# top.net
KiCad netlist of a schematic drawn in Altium Designer
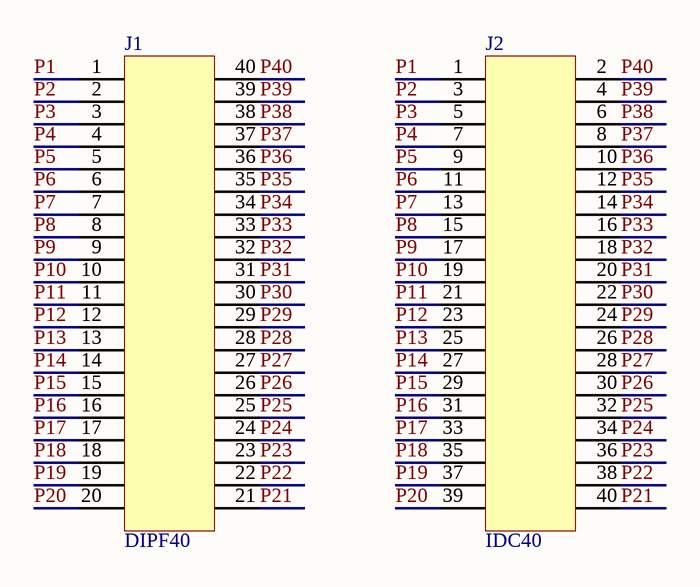
[diagram p0: top.SchDoc]

(export (version "E")
  (design (tool "Eeschema 10.0.6"))
  (components
    (comp (ref "J1")
      (value "DIPF40")
      (footprint "DIPF40")
      (description "DIP40 ZIF")
      (libsource (lib "schmlib") (part "DIPF40"))
    )
    (comp (ref "J2") (value "IDC40") (footprint "IDC40") (libsource (lib "schmlib") (part "IDC40")))
  )
  (nets
    (net (code "1") (name "/P1") (class "Default")
      (node (ref "J1") (pin "1") (pinfunction "1_1") (pintype "passive"))
      (node (ref "J2") (pin "1") (pinfunction "1_1") (pintype "passive"))
    )
    (net (code "2") (name "/P2") (class "Default")
      (node (ref "J1") (pin "2") (pinfunction "2_2") (pintype "passive"))
      (node (ref "J2") (pin "3") (pinfunction "3_3") (pintype "passive"))
    )
    (net (code "3") (name "/P3") (class "Default")
      (node (ref "J1") (pin "3") (pinfunction "3_3") (pintype "passive"))
      (node (ref "J2") (pin "5") (pinfunction "5_5") (pintype "passive"))
    )
    (net (code "4") (name "/P4") (class "Default")
      (node (ref "J1") (pin "4") (pinfunction "4_4") (pintype "passive"))
      (node (ref "J2") (pin "7") (pinfunction "7_7") (pintype "passive"))
    )
    (net (code "5") (name "/P5") (class "Default")
      (node (ref "J1") (pin "5") (pinfunction "5_5") (pintype "passive"))
      (node (ref "J2") (pin "9") (pinfunction "9_9") (pintype "passive"))
    )
    (net (code "6") (name "/P6") (class "Default")
      (node (ref "J1") (pin "6") (pinfunction "6_6") (pintype "passive"))
      (node (ref "J2") (pin "11") (pinfunction "11_11") (pintype "passive"))
    )
    (net (code "7") (name "/P7") (class "Default")
      (node (ref "J1") (pin "7") (pinfunction "7_7") (pintype "passive"))
      (node (ref "J2") (pin "13") (pinfunction "13_13") (pintype "passive"))
    )
    (net (code "8") (name "/P8") (class "Default")
      (node (ref "J1") (pin "8") (pinfunction "8_8") (pintype "passive"))
      (node (ref "J2") (pin "15") (pinfunction "15_15") (pintype "passive"))
    )
    (net (code "9") (name "/P9") (class "Default")
      (node (ref "J1") (pin "9") (pinfunction "9_9") (pintype "passive"))
      (node (ref "J2") (pin "17") (pinfunction "17_17") (pintype "passive"))
    )
    (net (code "10") (name "/P10") (class "Default")
      (node (ref "J1") (pin "10") (pinfunction "10_10") (pintype "passive"))
      (node (ref "J2") (pin "19") (pinfunction "19_19") (pintype "passive"))
    )
    (net (code "11") (name "/P11") (class "Default")
      (node (ref "J1") (pin "11") (pinfunction "11_11") (pintype "passive"))
      (node (ref "J2") (pin "21") (pinfunction "21_21") (pintype "passive"))
    )
    (net (code "12") (name "/P12") (class "Default")
      (node (ref "J1") (pin "12") (pinfunction "12_12") (pintype "passive"))
      (node (ref "J2") (pin "23") (pinfunction "23_23") (pintype "passive"))
    )
    (net (code "13") (name "/P13") (class "Default")
      (node (ref "J1") (pin "13") (pinfunction "13_13") (pintype "passive"))
      (node (ref "J2") (pin "25") (pinfunction "25_25") (pintype "passive"))
    )
    (net (code "14") (name "/P14") (class "Default")
      (node (ref "J1") (pin "14") (pinfunction "14_14") (pintype "passive"))
      (node (ref "J2") (pin "27") (pinfunction "27_27") (pintype "passive"))
    )
    (net (code "15") (name "/P15") (class "Default")
      (node (ref "J1") (pin "15") (pinfunction "15_15") (pintype "passive"))
      (node (ref "J2") (pin "29") (pinfunction "29_29") (pintype "passive"))
    )
    (net (code "16") (name "/P16") (class "Default")
      (node (ref "J1") (pin "16") (pinfunction "16_16") (pintype "passive"))
      (node (ref "J2") (pin "31") (pinfunction "31_31") (pintype "passive"))
    )
    (net (code "17") (name "/P17") (class "Default")
      (node (ref "J1") (pin "17") (pinfunction "17_17") (pintype "passive"))
      (node (ref "J2") (pin "33") (pinfunction "33_33") (pintype "passive"))
    )
    (net (code "18") (name "/P18") (class "Default")
      (node (ref "J1") (pin "18") (pinfunction "18_18") (pintype "passive"))
      (node (ref "J2") (pin "35") (pinfunction "35_35") (pintype "passive"))
    )
    (net (code "19") (name "/P19") (class "Default")
      (node (ref "J1") (pin "19") (pinfunction "19_19") (pintype "passive"))
      (node (ref "J2") (pin "37") (pinfunction "37_37") (pintype "passive"))
    )
    (net (code "20") (name "/P20") (class "Default")
      (node (ref "J1") (pin "20") (pinfunction "20_20") (pintype "passive"))
      (node (ref "J2") (pin "39") (pinfunction "39_39") (pintype "passive"))
    )
    (net (code "21") (name "/P21") (class "Default")
      (node (ref "J1") (pin "21") (pinfunction "21_21") (pintype "passive"))
      (node (ref "J2") (pin "40") (pinfunction "40_40") (pintype "passive"))
    )
    (net (code "22") (name "/P22") (class "Default")
      (node (ref "J1") (pin "22") (pinfunction "22_22") (pintype "passive"))
      (node (ref "J2") (pin "38") (pinfunction "38_38") (pintype "passive"))
    )
    (net (code "23") (name "/P23") (class "Default")
      (node (ref "J1") (pin "23") (pinfunction "23_23") (pintype "passive"))
      (node (ref "J2") (pin "36") (pinfunction "36_36") (pintype "passive"))
    )
    (net (code "24") (name "/P24") (class "Default")
      (node (ref "J1") (pin "24") (pinfunction "24_24") (pintype "passive"))
      (node (ref "J2") (pin "34") (pinfunction "34_34") (pintype "passive"))
    )
    (net (code "25") (name "/P25") (class "Default")
      (node (ref "J1") (pin "25") (pinfunction "25_25") (pintype "passive"))
      (node (ref "J2") (pin "32") (pinfunction "32_32") (pintype "passive"))
    )
    (net (code "26") (name "/P26") (class "Default")
      (node (ref "J1") (pin "26") (pinfunction "26_26") (pintype "passive"))
      (node (ref "J2") (pin "30") (pinfunction "30_30") (pintype "passive"))
    )
    (net (code "27") (name "/P27") (class "Default")
      (node (ref "J1") (pin "27") (pinfunction "27_27") (pintype "passive"))
      (node (ref "J2") (pin "28") (pinfunction "28_28") (pintype "passive"))
    )
    (net (code "28") (name "/P28") (class "Default")
      (node (ref "J1") (pin "28") (pinfunction "28_28") (pintype "passive"))
      (node (ref "J2") (pin "26") (pinfunction "26_26") (pintype "passive"))
    )
    (net (code "29") (name "/P29") (class "Default")
      (node (ref "J1") (pin "29") (pinfunction "29_29") (pintype "passive"))
      (node (ref "J2") (pin "24") (pinfunction "24_24") (pintype "passive"))
    )
    (net (code "30") (name "/P30") (class "Default")
      (node (ref "J1") (pin "30") (pinfunction "30_30") (pintype "passive"))
      (node (ref "J2") (pin "22") (pinfunction "22_22") (pintype "passive"))
    )
    (net (code "31") (name "/P31") (class "Default")
      (node (ref "J1") (pin "31") (pinfunction "31_31") (pintype "passive"))
      (node (ref "J2") (pin "20") (pinfunction "20_20") (pintype "passive"))
    )
    (net (code "32") (name "/P32") (class "Default")
      (node (ref "J1") (pin "32") (pinfunction "32_32") (pintype "passive"))
      (node (ref "J2") (pin "18") (pinfunction "18_18") (pintype "passive"))
    )
    (net (code "33") (name "/P33") (class "Default")
      (node (ref "J1") (pin "33") (pinfunction "33_33") (pintype "passive"))
      (node (ref "J2") (pin "16") (pinfunction "16_16") (pintype "passive"))
    )
    (net (code "34") (name "/P34") (class "Default")
      (node (ref "J1") (pin "34") (pinfunction "34_34") (pintype "passive"))
      (node (ref "J2") (pin "14") (pinfunction "14_14") (pintype "passive"))
    )
    (net (code "35") (name "/P35") (class "Default")
      (node (ref "J1") (pin "35") (pinfunction "35_35") (pintype "passive"))
      (node (ref "J2") (pin "12") (pinfunction "12_12") (pintype "passive"))
    )
    (net (code "36") (name "/P36") (class "Default")
      (node (ref "J1") (pin "36") (pinfunction "36_36") (pintype "passive"))
      (node (ref "J2") (pin "10") (pinfunction "10_10") (pintype "passive"))
    )
    (net (code "37") (name "/P37") (class "Default")
      (node (ref "J1") (pin "37") (pinfunction "37_37") (pintype "passive"))
      (node (ref "J2") (pin "8") (pinfunction "8_8") (pintype "passive"))
    )
    (net (code "38") (name "/P38") (class "Default")
      (node (ref "J1") (pin "38") (pinfunction "38_38") (pintype "passive"))
      (node (ref "J2") (pin "6") (pinfunction "6_6") (pintype "passive"))
    )
    (net (code "39") (name "/P39") (class "Default")
      (node (ref "J1") (pin "39") (pinfunction "39_39") (pintype "passive"))
      (node (ref "J2") (pin "4") (pinfunction "4_4") (pintype "passive"))
    )
    (net (code "40") (name "/P40") (class "Default")
      (node (ref "J1") (pin "40") (pinfunction "40_40") (pintype "passive"))
      (node (ref "J2") (pin "2") (pinfunction "2_2") (pintype "passive"))
    )
  )
)
